# Sheet_1_2023-04-10.net
KiCad netlist of a schematic drawn in Altium Designer
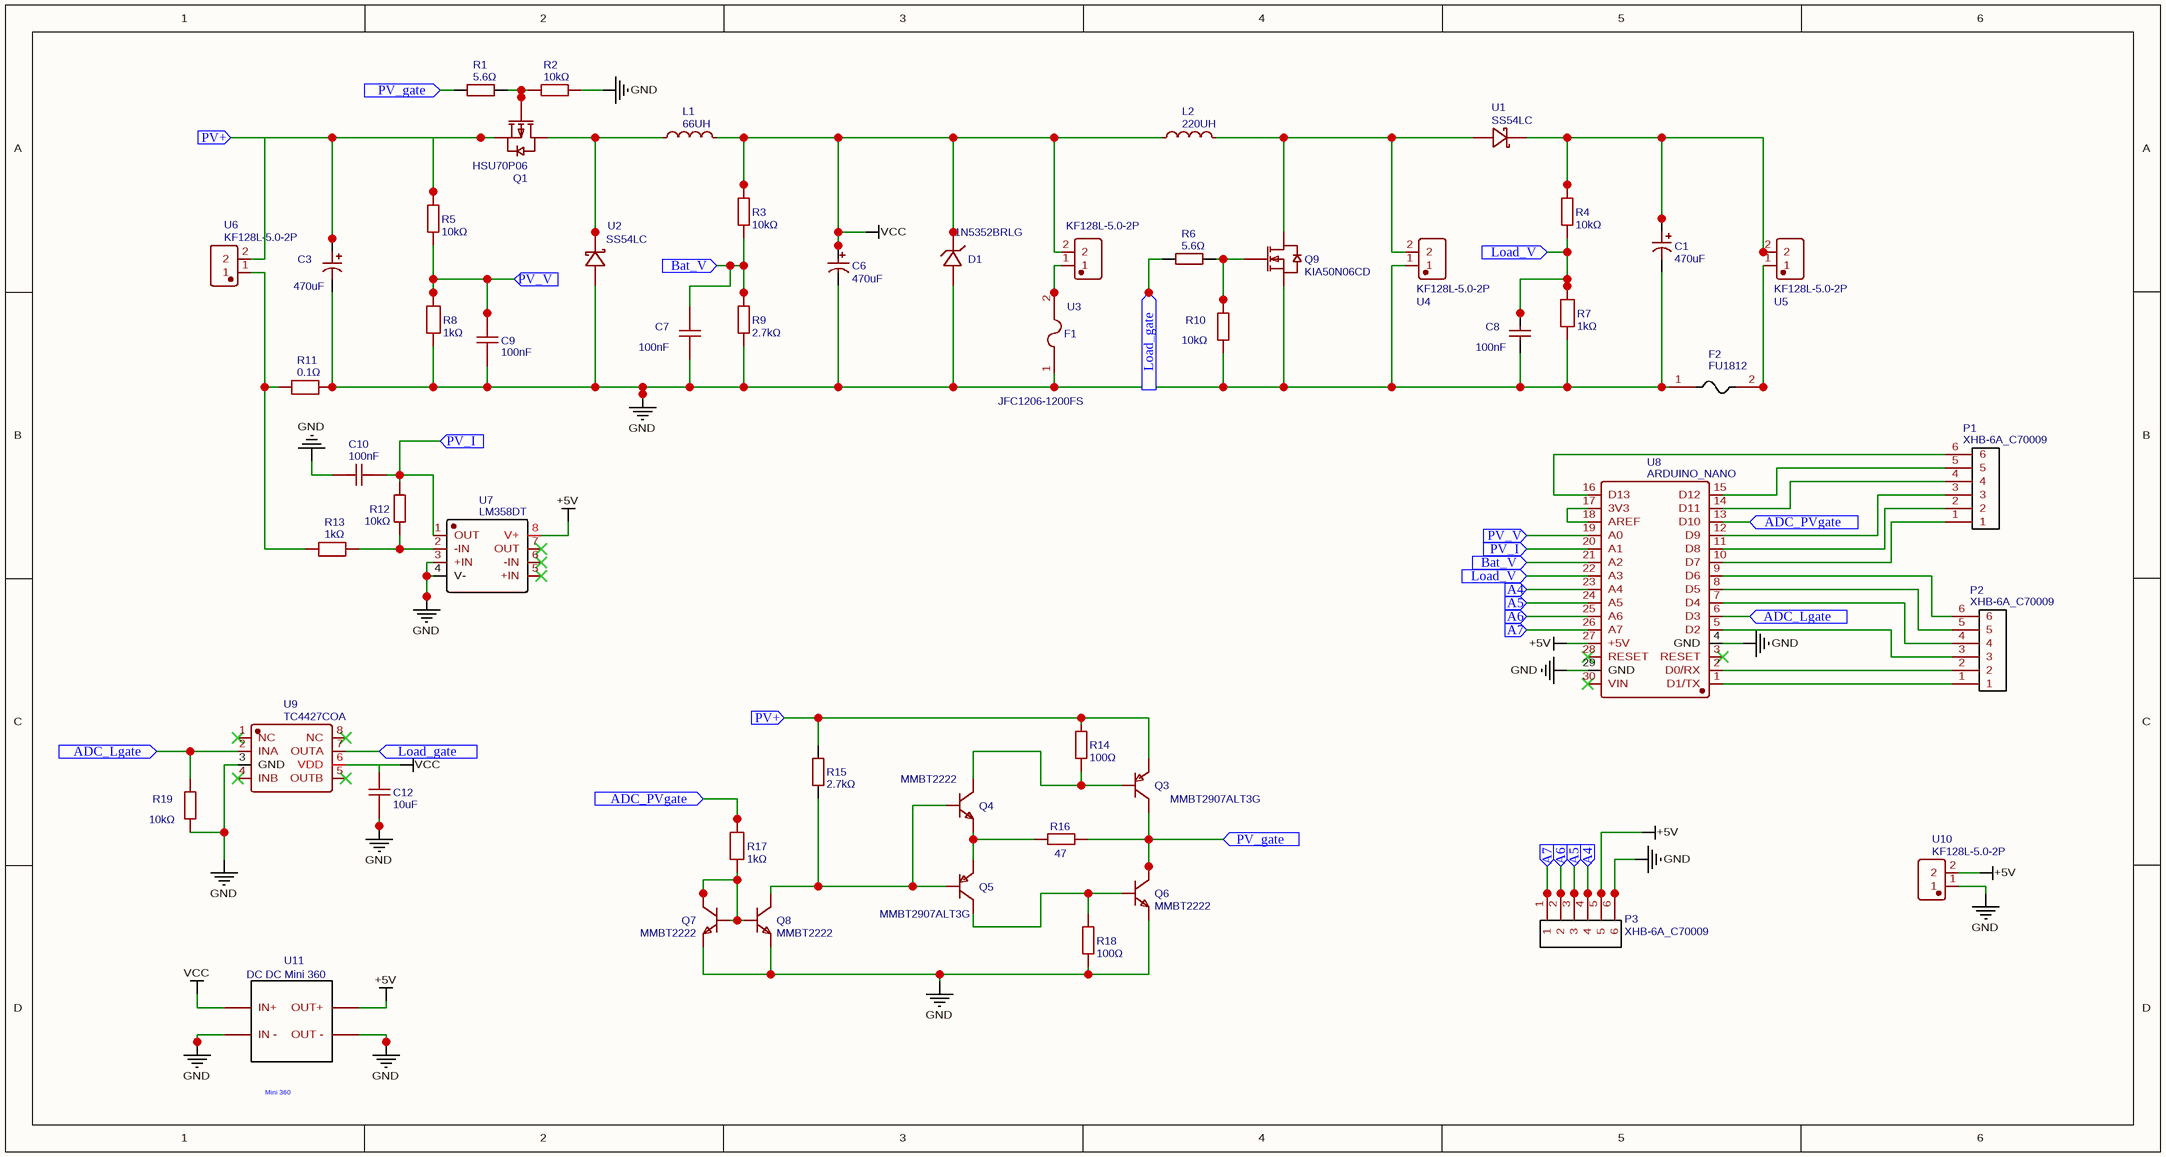
[diagram p0: Sheet_1_2023-04-10.schdoc]

(export (version "E")
  (design (tool "Eeschema 10.0.6"))
  (components
    (comp (ref "C1")
      (value "470uF")
      (fields
        (field (name "BOM_SUPPLIER PART") "C2960252")
        (field (name "BOM_MANUFACTURER PART") "35V470uF CD288")
        (field (name "CONTRIBUTOR") "LCSC")
      )
      (libsource (lib "") (part "root_3_470uF__1"))
    )
    (comp (ref "C3")
      (value "470uF")
      (fields
        (field (name "BOM_SUPPLIER PART") "C2960252")
        (field (name "BOM_MANUFACTURER PART") "35V470uF CD288")
        (field (name "CONTRIBUTOR") "LCSC")
      )
      (libsource (lib "") (part "root_3_470uF__1"))
    )
    (comp (ref "C6")
      (value "470uF")
      (fields
        (field (name "BOM_MANUFACTURER PART") "KM477M025G13RR0VH2FP0")
        (field (name "BOM_SUPPLIER PART") "C44594")
      )
      (libsource (lib "altium-import") (part "root_3_470uF_"))
    )
    (comp (ref "C7")
      (value "100nF")
      (fields
        (field (name "BOM_SUPPLIER PART") "C720961")
        (field (name "BOM_MANUFACTURER PART") "NL0805B104M500CPBN")
        (field (name "CONTRIBUTOR") "LCSC")
      )
      (libsource (lib "altium-import") (part "root_1_100nF_"))
    )
    (comp (ref "C8")
      (value "100nF")
      (fields
        (field (name "BOM_MANUFACTURER PART") "C0805X104K101T")
        (field (name "BOM_SUPPLIER PART") "C105951")
      )
      (libsource (lib "") (part "root_1_100nF__1"))
    )
    (comp (ref "C9")
      (value "100nF")
      (fields
        (field (name "BOM_SUPPLIER PART") "C720961")
        (field (name "BOM_MANUFACTURER PART") "NL0805B104M500CPBN")
        (field (name "CONTRIBUTOR") "LCSC")
      )
      (libsource (lib "altium-import") (part "root_1_100nF_"))
    )
    (comp (ref "C10")
      (value "100nF")
      (fields
        (field (name "BOM_SUPPLIER PART") "C720961")
        (field (name "BOM_MANUFACTURER PART") "NL0805B104M500CPBN")
        (field (name "CONTRIBUTOR") "LCSC")
      )
      (libsource (lib "altium-import") (part "root_2_100nF_"))
    )
    (comp (ref "C12")
      (value "10uF")
      (fields
        (field (name "BOM_SUPPLIER PART") "C2312016")
        (field (name "BOM_MANUFACTURER PART") "12066D106MAT4X")
        (field (name "CONTRIBUTOR") "LCSC")
      )
      (libsource (lib "altium-import") (part "root_1_10uF_"))
    )
    (comp (ref "D1")
      (value "1N5352BRLG")
      (fields (field (name "BOM_SUPPLIER PART") "C9711"))
      (libsource (lib "altium-import") (part "root_3_1N5352BRLG_"))
    )
    (comp (ref "F1")
      (value "JFC1206-1200FS")
      (fields (field (name "BOM_SUPPLIER PART") "C136345") (field (name "CONTRIBUTOR") "LCSC"))
      (libsource (lib "altium-import") (part "root_1_JFC1206-1200FS_"))
    )
    (comp (ref "F2")
      (value "FU1812")
      (fields (field (name "BOM_SUPPLIER PART") "C9900015946") (field (name "CONTRIBUTOR") "lcsc"))
      (libsource (lib "altium-import") (part "root_0_FU1812_"))
    )
    (comp (ref "L1")
      (value "66UH")
      (fields
        (field (name "BOM_SUPPLIER PART") "C9900026882")
        (field (name "BOM_MANUFACTURER PART") "47uH/10A")
        (field (name "CONTRIBUTOR") "lcsc")
      )
      (libsource (lib "altium-import") (part "root_0_66UH_"))
    )
    (comp (ref "L2")
      (value "220UH")
      (fields
        (field (name "BOM_SUPPLIER PART") "C9900026882")
        (field (name "BOM_MANUFACTURER PART") "47uH/10A")
        (field (name "CONTRIBUTOR") "lcsc")
      )
      (libsource (lib "altium-import") (part "root_0_220UH_"))
    )
    (comp (ref "P1")
      (value "XHB-6A_C70009")
      (fields (field (name "BOM_MANUFACTURER PART") "XHB-6A") (field (name "BOM_SUPPLIER PART") "C70009"))
      (libsource (lib "altium-import") (part "root_2_XHB-6A_C70009_"))
    )
    (comp (ref "P2")
      (value "XHB-6A_C70009")
      (fields (field (name "BOM_MANUFACTURER PART") "XHB-6A") (field (name "BOM_SUPPLIER PART") "C70009"))
      (libsource (lib "altium-import") (part "root_2_XHB-6A_C70009_"))
    )
    (comp (ref "P3")
      (value "XHB-6A_C70009")
      (fields (field (name "BOM_MANUFACTURER PART") "XHB-6A") (field (name "BOM_SUPPLIER PART") "C70009"))
      (libsource (lib "altium-import") (part "root_1_XHB-6A_C70009_"))
    )
    (comp (ref "Q1")
      (value "HSU70P06")
      (fields (field (name "BOM_SUPPLIER PART") "C2828492") (field (name "CONTRIBUTOR") "LCSC"))
      (libsource (lib "altium-import") (part "root_1_HSU70P06_"))
    )
    (comp (ref "Q3")
      (value "MMBT2907ALT3G")
      (fields (field (name "BOM_SUPPLIER PART") "C191231") (field (name "CONTRIBUTOR") "LCSC"))
      (libsource (lib "altium-import") (part "root_2_MMBT2907ALT3G_"))
    )
    (comp (ref "Q4")
      (value "MMBT2222")
      (fields (field (name "BOM_SUPPLIER PART") "C2891810") (field (name "CONTRIBUTOR") "LCSC"))
      (libsource (lib "altium-import") (part "root_0_MMBT2222_"))
    )
    (comp (ref "Q5")
      (value "MMBT2907ALT3G")
      (fields (field (name "BOM_SUPPLIER PART") "C191231") (field (name "CONTRIBUTOR") "LCSC"))
      (libsource (lib "altium-import") (part "root_2_MMBT2907ALT3G_"))
    )
    (comp (ref "Q6")
      (value "MMBT2222")
      (fields (field (name "BOM_SUPPLIER PART") "C2891810") (field (name "CONTRIBUTOR") "LCSC"))
      (libsource (lib "altium-import") (part "root_0_MMBT2222_"))
    )
    (comp (ref "Q7")
      (value "MMBT2222")
      (fields (field (name "BOM_SUPPLIER PART") "C2891810") (field (name "CONTRIBUTOR") "LCSC"))
      (libsource (lib "") (part "root_0_MMBT2222__1"))
    )
    (comp (ref "Q8")
      (value "MMBT2222")
      (fields (field (name "BOM_SUPPLIER PART") "C2891810") (field (name "CONTRIBUTOR") "LCSC"))
      (libsource (lib "altium-import") (part "root_0_MMBT2222_"))
    )
    (comp (ref "Q9")
      (value "KIA50N06CD")
      (fields (field (name "BOM_SUPPLIER PART") "C2931913") (field (name "CONTRIBUTOR") "LCSC"))
      (libsource (lib "altium-import") (part "root_0_KIA50N06CD_"))
    )
    (comp (ref "R1")
      (value "5.6Ω")
      (fields
        (field (name "BOM_MANUFACTURER PART") "CR0805J805R6G")
        (field (name "BOM_SUPPLIER PART") "C102035")
      )
      (libsource (lib "altium-import") (part "root_0_5.6Ω_"))
    )
    (comp (ref "R2")
      (value "10kΩ")
      (fields
        (field (name "BOM_SUPPLIER PART") "C253445")
        (field (name "BOM_MANUFACTURER PART") "MCR10EZPF1002")
        (field (name "CONTRIBUTOR") "LCSC")
      )
      (libsource (lib "altium-import") (part "root_2_10kΩ_"))
    )
    (comp (ref "R3")
      (value "10kΩ")
      (fields
        (field (name "BOM_SUPPLIER PART") "C253445")
        (field (name "BOM_MANUFACTURER PART") "MCR10EZPF1002")
        (field (name "CONTRIBUTOR") "LCSC")
      )
      (libsource (lib "altium-import") (part "root_1_10kΩ_"))
    )
    (comp (ref "R4")
      (value "10kΩ")
      (fields
        (field (name "BOM_SUPPLIER PART") "C253445")
        (field (name "BOM_MANUFACTURER PART") "MCR10EZPF1002")
        (field (name "CONTRIBUTOR") "LCSC")
      )
      (libsource (lib "altium-import") (part "root_1_10kΩ_"))
    )
    (comp (ref "R5")
      (value "10kΩ")
      (fields
        (field (name "BOM_SUPPLIER PART") "C253445")
        (field (name "BOM_MANUFACTURER PART") "MCR10EZPF1002")
        (field (name "CONTRIBUTOR") "LCSC")
      )
      (libsource (lib "altium-import") (part "root_1_10kΩ_"))
    )
    (comp (ref "R6")
      (value "5.6Ω")
      (fields
        (field (name "BOM_MANUFACTURER PART") "CR0805J805R6G")
        (field (name "BOM_SUPPLIER PART") "C102035")
      )
      (libsource (lib "altium-import") (part "root_0_5.6Ω_"))
    )
    (comp (ref "R7")
      (value "1kΩ")
      (fields
        (field (name "BOM_SUPPLIER PART") "C441981")
        (field (name "BOM_MANUFACTURER PART") "ERJP06F1001V")
        (field (name "CONTRIBUTOR") "LCSC")
      )
      (libsource (lib "altium-import") (part "root_1_1kΩ_"))
    )
    (comp (ref "R8")
      (value "1kΩ")
      (fields
        (field (name "BOM_SUPPLIER PART") "C441981")
        (field (name "BOM_MANUFACTURER PART") "ERJP06F1001V")
        (field (name "CONTRIBUTOR") "LCSC")
      )
      (libsource (lib "altium-import") (part "root_1_1kΩ_"))
    )
    (comp (ref "R9")
      (value "2.7kΩ")
      (fields
        (field (name "BOM_SUPPLIER PART") "C325950")
        (field (name "BOM_MANUFACTURER PART") "RMC08052.7K5%N")
        (field (name "CONTRIBUTOR") "LCSC")
      )
      (libsource (lib "altium-import") (part "root_1_2.7kΩ_"))
    )
    (comp (ref "R10")
      (value "10kΩ")
      (fields
        (field (name "BOM_SUPPLIER PART") "C253445")
        (field (name "BOM_MANUFACTURER PART") "MCR10EZPF1002")
        (field (name "CONTRIBUTOR") "LCSC")
      )
      (libsource (lib "altium-import") (part "root_1_10kΩ_"))
    )
    (comp (ref "R11")
      (value "0.1Ω")
      (fields
        (field (name "BOM_SUPPLIER PART") "C346817")
        (field (name "BOM_MANUFACTURER PART") "CSRN2512FTR100")
        (field (name "CONTRIBUTOR") "LCSC")
      )
      (libsource (lib "altium-import") (part "root_0_0.1Ω_"))
    )
    (comp (ref "R12")
      (value "10kΩ")
      (fields
        (field (name "BOM_SUPPLIER PART") "C253445")
        (field (name "BOM_MANUFACTURER PART") "MCR10EZPF1002")
        (field (name "CONTRIBUTOR") "LCSC")
      )
      (libsource (lib "altium-import") (part "root_3_10kΩ_"))
    )
    (comp (ref "R13")
      (value "1kΩ")
      (fields
        (field (name "BOM_SUPPLIER PART") "C441981")
        (field (name "BOM_MANUFACTURER PART") "ERJP06F1001V")
        (field (name "CONTRIBUTOR") "LCSC")
      )
      (libsource (lib "altium-import") (part "root_2_1kΩ_"))
    )
    (comp (ref "R14")
      (value "100Ω")
      (fields
        (field (name "BOM_SUPPLIER PART") "C328380")
        (field (name "BOM_MANUFACTURER PART") "AECR0805F100RK9")
        (field (name "CONTRIBUTOR") "LCSC")
      )
      (libsource (lib "altium-import") (part "root_3_100Ω_"))
    )
    (comp (ref "R15")
      (value "2.7kΩ")
      (fields
        (field (name "BOM_MANUFACTURER PART") "CR0805F82701G")
        (field (name "BOM_SUPPLIER PART") "C101616")
      )
      (libsource (lib "altium-import") (part "root_1_2.7kΩ_"))
    )
    (comp (ref "R16")
      (value "47")
      (fields
        (field (name "BOM_MANUFACTURER PART") "AC0805FR-0747RL")
        (field (name "BOM_SUPPLIER PART") "C144557")
        (field (name "CONTRIBUTOR") "LCSC")
      )
      (libsource (lib "altium-import") (part "root_0_47_"))
    )
    (comp (ref "R17")
      (value "1kΩ")
      (fields
        (field (name "BOM_SUPPLIER PART") "C441981")
        (field (name "BOM_MANUFACTURER PART") "ERJP06F1001V")
        (field (name "CONTRIBUTOR") "LCSC")
      )
      (libsource (lib "altium-import") (part "root_1_1kΩ_"))
    )
    (comp (ref "R18")
      (value "100Ω")
      (fields
        (field (name "BOM_SUPPLIER PART") "C328380")
        (field (name "BOM_MANUFACTURER PART") "AECR0805F100RK9")
        (field (name "CONTRIBUTOR") "LCSC")
      )
      (libsource (lib "altium-import") (part "root_3_100Ω_"))
    )
    (comp (ref "R19")
      (value "10kΩ")
      (fields
        (field (name "BOM_SUPPLIER PART") "C253445")
        (field (name "BOM_MANUFACTURER PART") "MCR10EZPF1002")
        (field (name "CONTRIBUTOR") "LCSC")
      )
      (libsource (lib "altium-import") (part "root_1_10kΩ_"))
    )
    (comp (ref "U1")
      (value "SS54LC")
      (fields (field (name "BOM_SUPPLIER PART") "C3033290") (field (name "CONTRIBUTOR") "lcsc"))
      (libsource (lib "altium-import") (part "root_2_SS54LC_"))
    )
    (comp (ref "U2")
      (value "SS54LC")
      (fields (field (name "BOM_SUPPLIER PART") "C3033290") (field (name "CONTRIBUTOR") "lcsc"))
      (libsource (lib "altium-import") (part "root_3_SS54LC_"))
    )
    (comp (ref "U3")
      (value "KF128L-5.0-2P")
      (fields (field (name "BOM_SUPPLIER PART") "C474938") (field (name "CONTRIBUTOR") "LCSC"))
      (libsource (lib "altium-import") (part "root_0_KF128L-5.0-2P_"))
    )
    (comp (ref "U4")
      (value "KF128L-5.0-2P")
      (fields (field (name "BOM_SUPPLIER PART") "C474938") (field (name "CONTRIBUTOR") "LCSC"))
      (libsource (lib "altium-import") (part "root_0_KF128L-5.0-2P_"))
    )
    (comp (ref "U5")
      (value "KF128L-5.0-2P")
      (fields (field (name "BOM_SUPPLIER PART") "C474938") (field (name "CONTRIBUTOR") "LCSC"))
      (libsource (lib "altium-import") (part "root_0_KF128L-5.0-2P_"))
    )
    (comp (ref "U6")
      (value "KF128L-5.0-2P")
      (fields (field (name "BOM_SUPPLIER PART") "C474938") (field (name "CONTRIBUTOR") "LCSC"))
      (libsource (lib "altium-import") (part "root_2_KF128L-5.0-2P_"))
    )
    (comp (ref "U7")
      (value "LM358DT")
      (fields (field (name "BOM_SUPPLIER PART") "C9418"))
      (libsource (lib "altium-import") (part "root_0_LM358DT_"))
    )
    (comp (ref "U8")
      (value "ARDUINO_NANO")
      (fields (field (name "BOM_SUPPLIER PART") "C9900017879") (field (name "CONTRIBUTOR") "lcsc"))
      (libsource (lib "altium-import") (part "root_2_ARDUINO_NANO_"))
    )
    (comp (ref "U9")
      (value "TC4427COA")
      (fields (field (name "BOM_SUPPLIER PART") "C636890") (field (name "CONTRIBUTOR") "lcsc"))
      (libsource (lib "altium-import") (part "root_0_TC4427COA_"))
    )
    (comp (ref "U10")
      (value "KF128L-5.0-2P")
      (fields (field (name "BOM_SUPPLIER PART") "C474938") (field (name "CONTRIBUTOR") "LCSC"))
      (libsource (lib "altium-import") (part "root_2_KF128L-5.0-2P_"))
    )
    (comp (ref "U11")
      (value "DC DC Mini 360")
      (fields (field (name "CONTRIBUTOR") "stanpak"))
      (libsource (lib "altium-import") (part "root_0_DC DC Mini 360_"))
    )
  )
  (nets
    (net (code "1") (name "+5V") (class "Default")
      (node (ref "P3") (pin "5") (pinfunction "5_5") (pintype "passive"))
      (node (ref "U10") (pin "2") (pinfunction "2_2") (pintype "passive"))
      (node (ref "U11") (pin "1") (pinfunction "OUT+_1") (pintype "passive"))
      (node (ref "U7") (pin "8") (pinfunction "V+_8") (pintype "passive"))
      (node (ref "U8") (pin "27") (pinfunction "+5V_27") (pintype "passive"))
    )
    (net (code "2") (name "/A4") (class "Default")
      (node (ref "P3") (pin "4") (pinfunction "4_4") (pintype "passive"))
      (node (ref "U8") (pin "23") (pinfunction "A4_23") (pintype "passive"))
    )
    (net (code "3") (name "/A5") (class "Default")
      (node (ref "P3") (pin "3") (pinfunction "3_3") (pintype "passive"))
      (node (ref "U8") (pin "24") (pinfunction "A5_24") (pintype "passive"))
    )
    (net (code "4") (name "/A6") (class "Default")
      (node (ref "P3") (pin "2") (pinfunction "2_2") (pintype "passive"))
      (node (ref "U8") (pin "25") (pinfunction "A6_25") (pintype "passive"))
    )
    (net (code "5") (name "/A7") (class "Default")
      (node (ref "P3") (pin "1") (pinfunction "1_1") (pintype "passive"))
      (node (ref "U8") (pin "26") (pinfunction "A7_26") (pintype "passive"))
    )
    (net (code "6") (name "/ADC_Lgate") (class "Default")
      (node (ref "R19") (pin "2") (pinfunction "2_2") (pintype "passive"))
      (node (ref "U8") (pin "6") (pinfunction "D3_6") (pintype "passive"))
      (node (ref "U9") (pin "2") (pinfunction "INA_2") (pintype "passive"))
    )
    (net (code "7") (name "/ADC_PVgate") (class "Default")
      (node (ref "R17") (pin "2") (pinfunction "2_2") (pintype "passive"))
      (node (ref "U8") (pin "13") (pinfunction "D10_13") (pintype "passive"))
    )
    (net (code "8") (name "/Bat_V") (class "Default")
      (node (ref "C7") (pin "2") (pinfunction "2_2") (pintype "passive"))
      (node (ref "R3") (pin "1") (pinfunction "1_1") (pintype "passive"))
      (node (ref "R9") (pin "2") (pinfunction "2_2") (pintype "passive"))
      (node (ref "U8") (pin "21") (pinfunction "A2_21") (pintype "passive"))
    )
    (net (code "9") (name "/Load_V") (class "Default")
      (node (ref "C8") (pin "2") (pinfunction "2_2") (pintype "passive"))
      (node (ref "R4") (pin "1") (pinfunction "1_1") (pintype "passive"))
      (node (ref "R7") (pin "2") (pinfunction "2_2") (pintype "passive"))
      (node (ref "U8") (pin "22") (pinfunction "A3_22") (pintype "passive"))
    )
    (net (code "10") (name "/Load_gate") (class "Default")
      (node (ref "R6") (pin "1") (pinfunction "1_1") (pintype "passive"))
      (node (ref "U9") (pin "7") (pinfunction "OUTA_7") (pintype "passive"))
    )
    (net (code "11") (name "/PV+") (class "Default")
      (node (ref "C3") (pin "1") (pinfunction "1_1") (pintype "passive"))
      (node (ref "Q1") (pin "3") (pinfunction "S_3") (pintype "passive"))
      (node (ref "Q3") (pin "2") (pinfunction "E_2") (pintype "passive"))
      (node (ref "R14") (pin "1") (pinfunction "1_1") (pintype "passive"))
      (node (ref "R15") (pin "2") (pinfunction "2_2") (pintype "passive"))
      (node (ref "R5") (pin "2") (pinfunction "2_2") (pintype "passive"))
      (node (ref "U6") (pin "2") (pinfunction "2_2") (pintype "passive"))
    )
    (net (code "12") (name "/PV_I") (class "Default")
      (node (ref "C10") (pin "1") (pinfunction "1_1") (pintype "passive"))
      (node (ref "R12") (pin "1") (pinfunction "1_1") (pintype "passive"))
      (node (ref "U7") (pin "1") (pinfunction "OUT_1") (pintype "passive"))
      (node (ref "U8") (pin "20") (pinfunction "A1_20") (pintype "passive"))
    )
    (net (code "13") (name "/PV_V") (class "Default")
      (node (ref "C9") (pin "2") (pinfunction "2_2") (pintype "passive"))
      (node (ref "R5") (pin "1") (pinfunction "1_1") (pintype "passive"))
      (node (ref "R8") (pin "2") (pinfunction "2_2") (pintype "passive"))
      (node (ref "U8") (pin "19") (pinfunction "A0_19") (pintype "passive"))
    )
    (net (code "14") (name "/PV_gate") (class "Default")
      (node (ref "Q3") (pin "3") (pinfunction "C_3") (pintype "passive"))
      (node (ref "Q6") (pin "3") (pinfunction "C_3") (pintype "passive"))
      (node (ref "R1") (pin "1") (pinfunction "1_1") (pintype "passive"))
      (node (ref "R16") (pin "2") (pinfunction "2_2") (pintype "passive"))
    )
    (net (code "15") (name "GND") (class "Default")
      (node (ref "C1") (pin "2") (pinfunction "2_2") (pintype "passive"))
      (node (ref "C10") (pin "2") (pinfunction "2_2") (pintype "passive"))
      (node (ref "C12") (pin "1") (pinfunction "1_1") (pintype "passive"))
      (node (ref "C3") (pin "2") (pinfunction "2_2") (pintype "passive"))
      (node (ref "C6") (pin "2") (pinfunction "2_2") (pintype "passive"))
      (node (ref "C7") (pin "1") (pinfunction "1_1") (pintype "passive"))
      (node (ref "C8") (pin "1") (pinfunction "1_1") (pintype "passive"))
      (node (ref "C9") (pin "1") (pinfunction "1_1") (pintype "passive"))
      (node (ref "D1") (pin "2") (pinfunction "A_2") (pintype "passive"))
      (node (ref "F1") (pin "1") (pinfunction "1_1") (pintype "passive"))
      (node (ref "F2") (pin "1") (pinfunction "1_1") (pintype "passive"))
      (node (ref "P3") (pin "6") (pinfunction "6_6") (pintype "passive"))
      (node (ref "Q6") (pin "2") (pinfunction "E_2") (pintype "passive"))
      (node (ref "Q7") (pin "2") (pinfunction "E_2") (pintype "passive"))
      (node (ref "Q8") (pin "2") (pinfunction "E_2") (pintype "passive"))
      (node (ref "Q9") (pin "3") (pinfunction "S_3") (pintype "passive"))
      (node (ref "R10") (pin "1") (pinfunction "1_1") (pintype "passive"))
      (node (ref "R11") (pin "2") (pinfunction "2_2") (pintype "passive"))
      (node (ref "R18") (pin "2") (pinfunction "2_2") (pintype "passive"))
      (node (ref "R19") (pin "1") (pinfunction "1_1") (pintype "passive"))
      (node (ref "R2") (pin "1") (pinfunction "1_1") (pintype "passive"))
      (node (ref "R7") (pin "1") (pinfunction "1_1") (pintype "passive"))
      (node (ref "R8") (pin "1") (pinfunction "1_1") (pintype "passive"))
      (node (ref "R9") (pin "1") (pinfunction "1_1") (pintype "passive"))
      (node (ref "U10") (pin "1") (pinfunction "1_1") (pintype "passive"))
      (node (ref "U11") (pin "2") (pinfunction "OUT_-_2") (pintype "passive"))
      (node (ref "U11") (pin "4") (pinfunction "IN_-_4") (pintype "passive"))
      (node (ref "U2") (pin "2") (pinfunction "A_2") (pintype "passive"))
      (node (ref "U4") (pin "1") (pinfunction "1_1") (pintype "passive"))
      (node (ref "U7") (pin "3") (pinfunction "+IN_3") (pintype "passive"))
      (node (ref "U7") (pin "4") (pinfunction "V-_4") (pintype "passive"))
      (node (ref "U8") (pin "29") (pinfunction "GND_29") (pintype "passive"))
      (node (ref "U8") (pin "4") (pinfunction "GND_4") (pintype "passive"))
      (node (ref "U9") (pin "3") (pinfunction "GND_3") (pintype "passive"))
    )
    (net (code "16") (name "Net-(F1-Pad2)") (class "Default")
      (node (ref "F1") (pin "2") (pinfunction "2_2") (pintype "passive"))
      (node (ref "U3") (pin "1") (pinfunction "1_1") (pintype "passive"))
    )
    (net (code "17") (name "Net-(F2-Pad2)") (class "Default")
      (node (ref "F2") (pin "2") (pinfunction "2_2") (pintype "passive"))
      (node (ref "U5") (pin "1") (pinfunction "1_1") (pintype "passive"))
    )
    (net (code "18") (name "Net-(Q1-D)") (class "Default")
      (node (ref "L1") (pin "1") (pinfunction "1_1") (pintype "passive"))
      (node (ref "Q1") (pin "2") (pinfunction "D_2") (pintype "passive"))
      (node (ref "U2") (pin "1") (pinfunction "K_1") (pintype "passive"))
    )
    (net (code "19") (name "Net-(Q1-G)") (class "Default")
      (node (ref "Q1") (pin "1") (pinfunction "G_1") (pintype "passive"))
      (node (ref "R1") (pin "2") (pinfunction "2_2") (pintype "passive"))
      (node (ref "R2") (pin "2") (pinfunction "2_2") (pintype "passive"))
    )
    (net (code "20") (name "Net-(Q3-B)") (class "Default")
      (node (ref "Q3") (pin "1") (pinfunction "B_1") (pintype "passive"))
      (node (ref "Q4") (pin "3") (pinfunction "C_3") (pintype "passive"))
      (node (ref "R14") (pin "2") (pinfunction "2_2") (pintype "passive"))
    )
    (net (code "21") (name "Net-(Q4-B)") (class "Default")
      (node (ref "Q4") (pin "1") (pinfunction "B_1") (pintype "passive"))
      (node (ref "Q5") (pin "1") (pinfunction "B_1") (pintype "passive"))
      (node (ref "Q8") (pin "3") (pinfunction "C_3") (pintype "passive"))
      (node (ref "R15") (pin "1") (pinfunction "1_1") (pintype "passive"))
    )
    (net (code "22") (name "Net-(Q4-E)") (class "Default")
      (node (ref "Q4") (pin "2") (pinfunction "E_2") (pintype "passive"))
      (node (ref "Q5") (pin "2") (pinfunction "E_2") (pintype "passive"))
      (node (ref "R16") (pin "1") (pinfunction "1_1") (pintype "passive"))
    )
    (net (code "23") (name "Net-(Q5-C)") (class "Default")
      (node (ref "Q5") (pin "3") (pinfunction "C_3") (pintype "passive"))
      (node (ref "Q6") (pin "1") (pinfunction "B_1") (pintype "passive"))
      (node (ref "R18") (pin "1") (pinfunction "1_1") (pintype "passive"))
    )
    (net (code "24") (name "Net-(Q7-B)") (class "Default")
      (node (ref "Q7") (pin "1") (pinfunction "B_1") (pintype "passive"))
      (node (ref "Q7") (pin "3") (pinfunction "C_3") (pintype "passive"))
      (node (ref "Q8") (pin "1") (pinfunction "B_1") (pintype "passive"))
      (node (ref "R17") (pin "1") (pinfunction "1_1") (pintype "passive"))
    )
    (net (code "25") (name "Net-(Q9-D)") (class "Default")
      (node (ref "L2") (pin "2") (pinfunction "2_2") (pintype "passive"))
      (node (ref "Q9") (pin "2") (pinfunction "D_2") (pintype "passive"))
      (node (ref "U1") (pin "2") (pinfunction "A_2") (pintype "passive"))
      (node (ref "U4") (pin "2") (pinfunction "2_2") (pintype "passive"))
    )
    (net (code "26") (name "Net-(Q9-G)") (class "Default")
      (node (ref "Q9") (pin "1") (pinfunction "G_1") (pintype "passive"))
      (node (ref "R10") (pin "2") (pinfunction "2_2") (pintype "passive"))
      (node (ref "R6") (pin "2") (pinfunction "2_2") (pintype "passive"))
    )
    (net (code "27") (name "Net-(R11-Pad1)") (class "Default")
      (node (ref "R11") (pin "1") (pinfunction "1_1") (pintype "passive"))
      (node (ref "R13") (pin "2") (pinfunction "2_2") (pintype "passive"))
      (node (ref "U6") (pin "1") (pinfunction "1_1") (pintype "passive"))
    )
    (net (code "28") (name "Net-(R12-Pad2)") (class "Default")
      (node (ref "R12") (pin "2") (pinfunction "2_2") (pintype "passive"))
      (node (ref "R13") (pin "1") (pinfunction "1_1") (pintype "passive"))
      (node (ref "U7") (pin "2") (pinfunction "-IN_2") (pintype "passive"))
    )
    (net (code "29") (name "Net-(U1-K)") (class "Default")
      (node (ref "C1") (pin "1") (pinfunction "1_1") (pintype "passive"))
      (node (ref "R4") (pin "2") (pinfunction "2_2") (pintype "passive"))
      (node (ref "U1") (pin "1") (pinfunction "K_1") (pintype "passive"))
      (node (ref "U5") (pin "2") (pinfunction "2_2") (pintype "passive"))
    )
    (net (code "30") (name "Net-(U8-3V3)") (class "Default")
      (node (ref "U8") (pin "17") (pinfunction "3V3_17") (pintype "passive"))
      (node (ref "U8") (pin "18") (pinfunction "AREF_18") (pintype "passive"))
    )
    (net (code "31") (name "Net-(U8-D0{slash}RX)") (class "Default")
      (node (ref "P2") (pin "2") (pinfunction "2_2") (pintype "passive"))
      (node (ref "U8") (pin "2") (pinfunction "D0/RX_2") (pintype "passive"))
    )
    (net (code "32") (name "Net-(U8-D1{slash}TX)") (class "Default")
      (node (ref "P2") (pin "1") (pinfunction "1_1") (pintype "passive"))
      (node (ref "U8") (pin "1") (pinfunction "D1/TX_1") (pintype "passive"))
    )
    (net (code "33") (name "Net-(U8-D2)") (class "Default")
      (node (ref "P2") (pin "3") (pinfunction "3_3") (pintype "passive"))
      (node (ref "U8") (pin "5") (pinfunction "D2_5") (pintype "passive"))
    )
    (net (code "34") (name "Net-(U8-D4)") (class "Default")
      (node (ref "P2") (pin "4") (pinfunction "4_4") (pintype "passive"))
      (node (ref "U8") (pin "7") (pinfunction "D4_7") (pintype "passive"))
    )
    (net (code "35") (name "Net-(U8-D5)") (class "Default")
      (node (ref "P2") (pin "5") (pinfunction "5_5") (pintype "passive"))
      (node (ref "U8") (pin "8") (pinfunction "D5_8") (pintype "passive"))
    )
    (net (code "36") (name "Net-(U8-D6)") (class "Default")
      (node (ref "P2") (pin "6") (pinfunction "6_6") (pintype "passive"))
      (node (ref "U8") (pin "9") (pinfunction "D6_9") (pintype "passive"))
    )
    (net (code "37") (name "Net-(U8-D7)") (class "Default")
      (node (ref "P1") (pin "1") (pinfunction "1_1") (pintype "passive"))
      (node (ref "U8") (pin "10") (pinfunction "D7_10") (pintype "passive"))
    )
    (net (code "38") (name "Net-(U8-D8)") (class "Default")
      (node (ref "P1") (pin "2") (pinfunction "2_2") (pintype "passive"))
      (node (ref "U8") (pin "11") (pinfunction "D8_11") (pintype "passive"))
    )
    (net (code "39") (name "Net-(U8-D9)") (class "Default")
      (node (ref "P1") (pin "3") (pinfunction "3_3") (pintype "passive"))
      (node (ref "U8") (pin "12") (pinfunction "D9_12") (pintype "passive"))
    )
    (net (code "40") (name "Net-(U8-D11)") (class "Default")
      (node (ref "P1") (pin "4") (pinfunction "4_4") (pintype "passive"))
      (node (ref "U8") (pin "14") (pinfunction "D11_14") (pintype "passive"))
    )
    (net (code "41") (name "Net-(U8-D12)") (class "Default")
      (node (ref "P1") (pin "5") (pinfunction "5_5") (pintype "passive"))
      (node (ref "U8") (pin "15") (pinfunction "D12_15") (pintype "passive"))
    )
    (net (code "42") (name "Net-(U8-D13)") (class "Default")
      (node (ref "P1") (pin "6") (pinfunction "6_6") (pintype "passive"))
      (node (ref "U8") (pin "16") (pinfunction "D13_16") (pintype "passive"))
    )
    (net (code "43") (name "VCC") (class "Default")
      (node (ref "C12") (pin "2") (pinfunction "2_2") (pintype "passive"))
      (node (ref "C6") (pin "1") (pinfunction "1_1") (pintype "passive"))
      (node (ref "D1") (pin "1") (pinfunction "K_1") (pintype "passive"))
      (node (ref "L1") (pin "2") (pinfunction "2_2") (pintype "passive"))
      (node (ref "L2") (pin "1") (pinfunction "1_1") (pintype "passive"))
      (node (ref "R3") (pin "2") (pinfunction "2_2") (pintype "passive"))
      (node (ref "U11") (pin "3") (pinfunction "IN+_3") (pintype "passive"))
      (node (ref "U3") (pin "2") (pinfunction "2_2") (pintype "passive"))
      (node (ref "U9") (pin "6") (pinfunction "VDD_6") (pintype "passive"))
    )
    (net (code "44") (name "unconnected-(U7-+IN-Pad5)") (class "Default")
      (node (ref "U7") (pin "5") (pinfunction "+IN_5") (pintype "passive+no_connect"))
    )
    (net (code "45") (name "unconnected-(U7--IN-Pad6)") (class "Default")
      (node (ref "U7") (pin "6") (pinfunction "-IN_6") (pintype "passive+no_connect"))
    )
    (net (code "46") (name "unconnected-(U7-OUT-Pad7)") (class "Default")
      (node (ref "U7") (pin "7") (pinfunction "OUT_7") (pintype "passive+no_connect"))
    )
    (net (code "47") (name "unconnected-(U8-RESET-Pad3)") (class "Default")
      (node (ref "U8") (pin "3") (pinfunction "RESET_3") (pintype "passive+no_connect"))
    )
    (net (code "48") (name "unconnected-(U8-RESET-Pad28)") (class "Default")
      (node (ref "U8") (pin "28") (pinfunction "RESET_28") (pintype "passive+no_connect"))
    )
    (net (code "49") (name "unconnected-(U8-VIN-Pad30)") (class "Default")
      (node (ref "U8") (pin "30") (pinfunction "VIN_30") (pintype "passive+no_connect"))
    )
    (net (code "50") (name "unconnected-(U9-INB-Pad4)") (class "Default")
      (node (ref "U9") (pin "4") (pinfunction "INB_4") (pintype "passive+no_connect"))
    )
    (net (code "51") (name "unconnected-(U9-NC-Pad1)") (class "Default")
      (node (ref "U9") (pin "1") (pinfunction "NC_1") (pintype "passive+no_connect"))
    )
    (net (code "52") (name "unconnected-(U9-NC-Pad8)") (class "Default")
      (node (ref "U9") (pin "8") (pinfunction "NC_8") (pintype "passive+no_connect"))
    )
    (net (code "53") (name "unconnected-(U9-OUTB-Pad5)") (class "Default")
      (node (ref "U9") (pin "5") (pinfunction "OUTB_5") (pintype "passive+no_connect"))
    )
  )
)
